# digital_output_amp.net
KiCad netlist of a schematic drawn in EAGLE
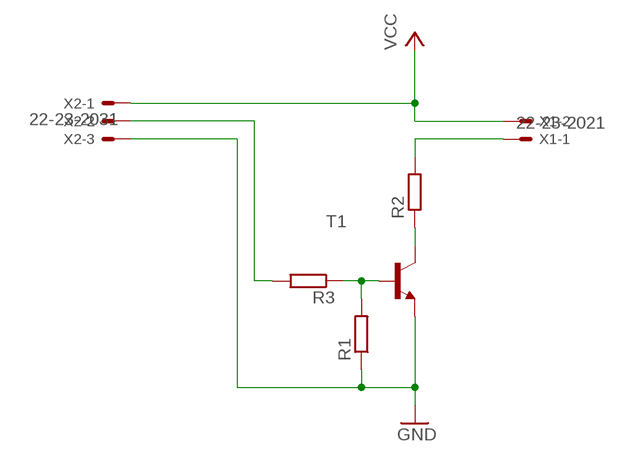
[diagram p0: schematic, sheet 1]

(export (version "E")
  (design (tool "Eeschema 10.0.6"))
  (components
    (comp (ref "R1")
      (value "R-EU_M1206")
      (footprint "eagle-import:M1206")
      (libsource (lib "eagle-import") (part "R-EU_M1206"))
    )
    (comp (ref "R2")
      (value "R-EU_M1206")
      (footprint "eagle-import:M1206")
      (libsource (lib "eagle-import") (part "R-EU_M1206"))
    )
    (comp (ref "R3")
      (value "R-EU_M1206")
      (footprint "eagle-import:M1206")
      (libsource (lib "eagle-import") (part "R-EU_M1206"))
    )
    (comp (ref "T1")
      (value "BC817-40-NPN-SOT23-BEC")
      (footprint "eagle-import:SOT23-BEC")
      (libsource (lib "eagle-import") (part "-NPN-SOT23-BECBC817-40"))
    )
    (comp (ref "X1")
      (value "22-23-2021")
      (footprint "eagle-import:22-23-2021")
      (fields (field (name "MF") "MOLEX"))
      (libsource (lib "eagle-import") (part "22-23-2021"))
    )
    (comp (ref "X2")
      (value "22-23-2031")
      (footprint "eagle-import:22-23-2031")
      (fields (field (name "MF") "MOLEX"))
      (libsource (lib "eagle-import") (part "22-23-2031"))
    )
  )
  (nets
    (net (code "1") (name "GND") (class "Default")
      (node (ref "R1") (pin "1") (pinfunction "1_1") (pintype "passive"))
      (node (ref "T1") (pin "E") (pinfunction "E_E") (pintype "passive"))
      (node (ref "X2") (pin "3") (pinfunction "S_3") (pintype "passive"))
    )
    (net (code "2") (name "Net-(R1-Pad2)") (class "Default")
      (node (ref "R1") (pin "2") (pinfunction "2_2") (pintype "passive"))
      (node (ref "R3") (pin "1") (pinfunction "1_1") (pintype "passive"))
      (node (ref "T1") (pin "B") (pinfunction "B_B") (pintype "passive"))
    )
    (net (code "3") (name "Net-(R2-Pad1)") (class "Default")
      (node (ref "R2") (pin "1") (pinfunction "1_1") (pintype "passive"))
      (node (ref "T1") (pin "C") (pinfunction "C_C") (pintype "passive"))
    )
    (net (code "4") (name "Net-(X1A-S)") (class "Default")
      (node (ref "R2") (pin "2") (pinfunction "2_2") (pintype "passive"))
      (node (ref "X1") (pin "1") (pinfunction "S_1") (pintype "passive"))
    )
    (net (code "5") (name "Net-(X2B-S)") (class "Default")
      (node (ref "R3") (pin "2") (pinfunction "2_2") (pintype "passive"))
      (node (ref "X2") (pin "2") (pinfunction "S_2") (pintype "passive"))
    )
    (net (code "6") (name "VCC") (class "Default")
      (node (ref "X1") (pin "2") (pinfunction "S_2") (pintype "passive"))
      (node (ref "X2") (pin "1") (pinfunction "S_1") (pintype "passive"))
    )
  )
)
